# Picobox.net
KiCad netlist of a schematic drawn in EasyEDA
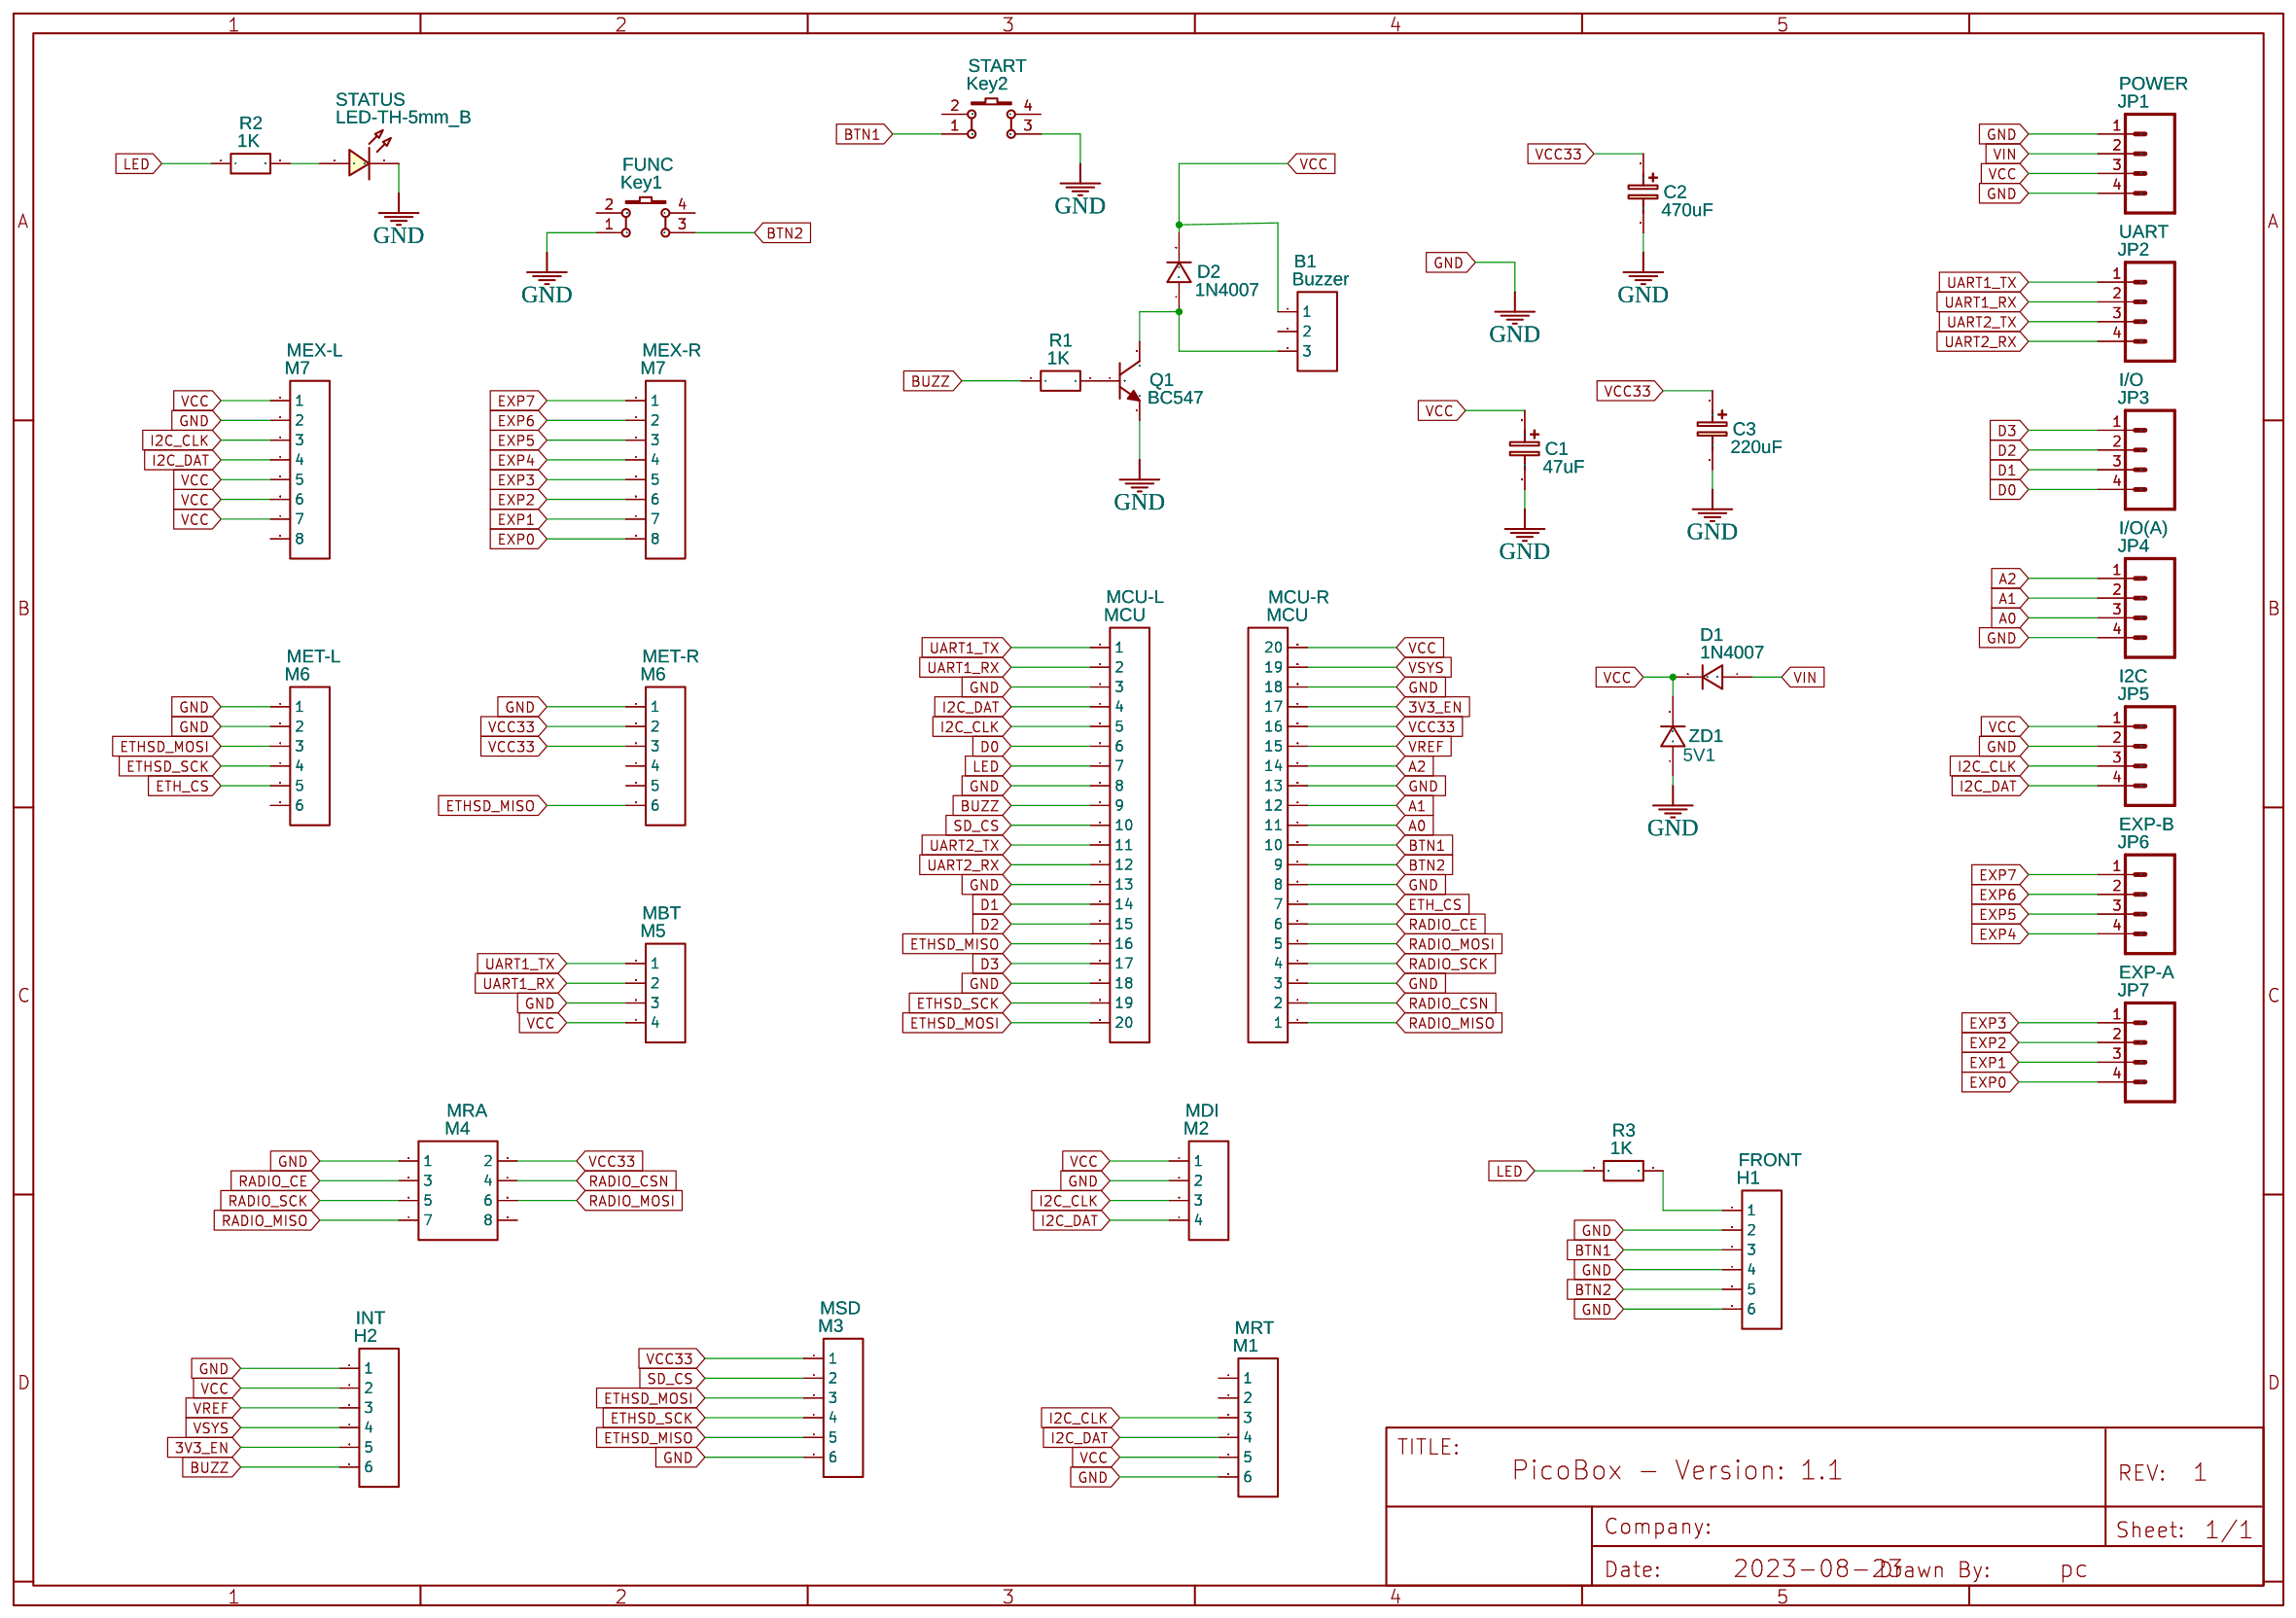
[diagram p0: schematic sheet]

(export (version "E")
  (design (tool "Eeschema 10.0.6"))
  (components
    (comp (ref "B1")
      (value "Buzzer")
      (fields (field (name "BOM_Supplier Part") "C146690"))
      (libsource (lib "") (part "HDR-F-2.54_1x3"))
    )
    (comp (ref "C1") (value "47uF") (libsource (lib "") (part "C_Tan_SMD_A_EU")))
    (comp (ref "C2") (value "470uF") (libsource (lib "") (part "C_Tan_SMD_A_EU")))
    (comp (ref "C3") (value "220uF") (libsource (lib "") (part "C_Tan_SMD_A_EU")))
    (comp (ref "D1")
      (value "1N4007")
      (fields (field (name "BOM_Manufacturer Part") "1N4007W") (field (name "BOM_Supplier Part") "C328592"))
      (libsource (lib "") (part "1N4007W_1"))
    )
    (comp (ref "D2")
      (value "1N4007")
      (fields (field (name "BOM_Manufacturer Part") "1N4007W") (field (name "BOM_Supplier Part") "C328592"))
      (libsource (lib "") (part "1N4007W"))
    )
    (comp (ref "EXP-A") (value "JP7") (libsource (lib "") (part "M04SCREW_4")))
    (comp (ref "EXP-B") (value "JP6") (libsource (lib "") (part "M04SCREW")))
    (comp (ref "FRONT")
      (value "H1")
      (fields (field (name "BOM_Supplier Part") "C40877"))
      (libsource (lib "") (part "HDR-F-2.54_1x6_5"))
    )
    (comp (ref "FUNC")
      (value "Key1")
      (fields
        (field (name "BOM_Manufacturer Part") "K2-1102DP-E4SW-04")
        (field (name "BOM_Supplier Part") "C136684")
      )
      (libsource (lib "") (part "K4-6×6_TH"))
    )
    (comp (ref "I/O") (value "JP3") (libsource (lib "") (part "M04SCREW_3")))
    (comp (ref "I/O(A)") (value "JP4") (libsource (lib "") (part "M04SCREW_1")))
    (comp (ref "I2C") (value "JP5") (libsource (lib "") (part "M04SCREW_5")))
    (comp (ref "INT")
      (value "H2")
      (fields (field (name "BOM_Supplier Part") "C40877"))
      (libsource (lib "") (part "HDR-F-2.54_1x6"))
    )
    (comp (ref "MBT")
      (value "M5")
      (fields (field (name "BOM_Supplier Part") "C225501"))
      (libsource (lib "") (part "HDR-F-2.54_1x4_1"))
    )
    (comp (ref "MCU-L")
      (value "MCU")
      (fields (field (name "BOM_Supplier Part") "C50984"))
      (libsource (lib "") (part "HDR-F-2.54_1x20_1"))
    )
    (comp (ref "MCU-R")
      (value "MCU")
      (fields (field (name "BOM_Supplier Part") "C50984"))
      (libsource (lib "") (part "HDR-F-2.54_1x20"))
    )
    (comp (ref "MDI")
      (value "M2")
      (fields (field (name "BOM_Supplier Part") "C225501"))
      (libsource (lib "") (part "HDR-F-2.54_1x4"))
    )
    (comp (ref "MET-L")
      (value "M6")
      (fields (field (name "BOM_Supplier Part") "C40877"))
      (libsource (lib "") (part "HDR-F-2.54_1x6_3"))
    )
    (comp (ref "MET-R")
      (value "M6")
      (fields (field (name "BOM_Supplier Part") "C40877"))
      (libsource (lib "") (part "HDR-F-2.54_1x6_1"))
    )
    (comp (ref "MEX-L")
      (value "M7")
      (fields (field (name "BOM_Supplier Part") "C225505"))
      (libsource (lib "") (part "HDR-F-2.54_1x8_1"))
    )
    (comp (ref "MEX-R")
      (value "M7")
      (fields (field (name "BOM_Supplier Part") "C225505"))
      (libsource (lib "") (part "HDR-F-2.54_1x8"))
    )
    (comp (ref "MRA")
      (value "M4")
      (fields (field (name "BOM_Supplier Part") "C239344"))
      (libsource (lib "") (part "HDR-F-2.54_2x4"))
    )
    (comp (ref "MRT")
      (value "M1")
      (fields (field (name "BOM_Supplier Part") "C40877"))
      (libsource (lib "") (part "HDR-F-2.54_1x6_2"))
    )
    (comp (ref "MSD")
      (value "M3")
      (fields (field (name "BOM_Supplier Part") "C40877"))
      (libsource (lib "") (part "HDR-F-2.54_1x6_4"))
    )
    (comp (ref "POWER") (value "JP1") (libsource (lib "") (part "M04SCREW_2")))
    (comp (ref "Q1")
      (value "BC547")
      (fields
        (field (name "BOM_Manufacturer Part") "2n3904S-RTK/PS")
        (field (name "BOM_Supplier Part") "C18536")
      )
      (libsource (lib "") (part "2N3904(SOT-23)"))
    )
    (comp (ref "R1") (value "1K") (libsource (lib "") (part "R_0603_EU")))
    (comp (ref "R2") (value "1K") (libsource (lib "") (part "R_0603_EU")))
    (comp (ref "R3") (value "1K") (libsource (lib "") (part "R_0603_EU")))
    (comp (ref "START")
      (value "Key2")
      (fields
        (field (name "BOM_Manufacturer Part") "K2-1102DP-E4SW-04")
        (field (name "BOM_Supplier Part") "C136684")
      )
      (libsource (lib "") (part "K4-6×6_TH_1"))
    )
    (comp (ref "STATUS")
      (value "LED-TH-5mm_B")
      (fields
        (field (name "BOM_Manufacturer Part") "333-2SYGD/S530-E2")
        (field (name "BOM_Supplier Part") "C88163")
      )
      (libsource (lib "") (part "LED-TH-5mm_G"))
    )
    (comp (ref "UART") (value "JP2") (libsource (lib "") (part "M04SCREW_6")))
    (comp (ref "ZD1")
      (value "1N4001")
      (fields (field (name "BOM_Manufacturer Part") "1N4007W") (field (name "BOM_Supplier Part") "C328592"))
      (libsource (lib "") (part "1N4007W_2"))
    )
  )
  (nets
    (net (code "1") (name "3V3_EN") (class "Default")
      (node (ref "INT") (pin "5") (pinfunction "5_5") (pintype "input"))
      (node (ref "MCU-R") (pin "17") (pinfunction "17_17") (pintype "unspecified"))
    )
    (net (code "2") (name "A0") (class "Default")
      (node (ref "I/O(A)") (pin "3") (pinfunction "3_3") (pintype "bidirectional"))
      (node (ref "MCU-R") (pin "11") (pinfunction "11_11") (pintype "unspecified"))
    )
    (net (code "3") (name "A1") (class "Default")
      (node (ref "I/O(A)") (pin "2") (pinfunction "2_2") (pintype "bidirectional"))
      (node (ref "MCU-R") (pin "12") (pinfunction "12_12") (pintype "unspecified"))
    )
    (net (code "4") (name "A2") (class "Default")
      (node (ref "I/O(A)") (pin "1") (pinfunction "1_1") (pintype "bidirectional"))
      (node (ref "MCU-R") (pin "14") (pinfunction "14_14") (pintype "unspecified"))
    )
    (net (code "5") (name "BTN1") (class "Default")
      (node (ref "FRONT") (pin "3") (pinfunction "3_3") (pintype "input"))
      (node (ref "MCU-R") (pin "10") (pinfunction "10_10") (pintype "unspecified"))
      (node (ref "START") (pin "1") (pinfunction "1_1") (pintype "unspecified"))
    )
    (net (code "6") (name "BTN2") (class "Default")
      (node (ref "FRONT") (pin "5") (pinfunction "5_5") (pintype "input"))
      (node (ref "FUNC") (pin "3") (pinfunction "3_3") (pintype "unspecified"))
      (node (ref "MCU-R") (pin "9") (pinfunction "9_9") (pintype "unspecified"))
    )
    (net (code "7") (name "BUZZ") (class "Default")
      (node (ref "INT") (pin "6") (pinfunction "6_6") (pintype "input"))
      (node (ref "MCU-L") (pin "9") (pinfunction "9_9") (pintype "unspecified"))
      (node (ref "R1") (pin "1") (pinfunction "1_1") (pintype "unspecified"))
    )
    (net (code "8") (name "D0") (class "Default")
      (node (ref "I/O") (pin "4") (pinfunction "4_4") (pintype "bidirectional"))
      (node (ref "MCU-L") (pin "6") (pinfunction "6_6") (pintype "unspecified"))
    )
    (net (code "9") (name "D1") (class "Default")
      (node (ref "I/O") (pin "3") (pinfunction "3_3") (pintype "bidirectional"))
      (node (ref "MCU-L") (pin "14") (pinfunction "14_14") (pintype "unspecified"))
    )
    (net (code "10") (name "D2") (class "Default")
      (node (ref "I/O") (pin "2") (pinfunction "2_2") (pintype "bidirectional"))
      (node (ref "MCU-L") (pin "15") (pinfunction "15_15") (pintype "unspecified"))
    )
    (net (code "11") (name "D3") (class "Default")
      (node (ref "I/O") (pin "1") (pinfunction "1_1") (pintype "bidirectional"))
      (node (ref "MCU-L") (pin "17") (pinfunction "17_17") (pintype "unspecified"))
    )
    (net (code "12") (name "ETHSD_MISO") (class "Default")
      (node (ref "MCU-L") (pin "16") (pinfunction "16_16") (pintype "unspecified"))
      (node (ref "MET-R") (pin "6") (pinfunction "6_6") (pintype "input"))
      (node (ref "MSD") (pin "5") (pinfunction "5_5") (pintype "input"))
    )
    (net (code "13") (name "ETHSD_MOSI") (class "Default")
      (node (ref "MCU-L") (pin "20") (pinfunction "20_20") (pintype "unspecified"))
      (node (ref "MET-L") (pin "3") (pinfunction "3_3") (pintype "input"))
      (node (ref "MSD") (pin "3") (pinfunction "3_3") (pintype "input"))
    )
    (net (code "14") (name "ETHSD_SCK") (class "Default")
      (node (ref "MCU-L") (pin "19") (pinfunction "19_19") (pintype "unspecified"))
      (node (ref "MET-L") (pin "4") (pinfunction "4_4") (pintype "input"))
      (node (ref "MSD") (pin "4") (pinfunction "4_4") (pintype "input"))
    )
    (net (code "15") (name "ETH_CS") (class "Default")
      (node (ref "MCU-R") (pin "7") (pinfunction "7_7") (pintype "unspecified"))
      (node (ref "MET-L") (pin "5") (pinfunction "5_5") (pintype "input"))
    )
    (net (code "16") (name "EXP0") (class "Default")
      (node (ref "EXP-A") (pin "4") (pinfunction "4_4") (pintype "bidirectional"))
      (node (ref "MEX-R") (pin "8") (pinfunction "8_8") (pintype "unspecified"))
    )
    (net (code "17") (name "EXP1") (class "Default")
      (node (ref "EXP-A") (pin "3") (pinfunction "3_3") (pintype "bidirectional"))
      (node (ref "MEX-R") (pin "7") (pinfunction "7_7") (pintype "unspecified"))
    )
    (net (code "18") (name "EXP2") (class "Default")
      (node (ref "EXP-A") (pin "2") (pinfunction "2_2") (pintype "bidirectional"))
      (node (ref "MEX-R") (pin "6") (pinfunction "6_6") (pintype "unspecified"))
    )
    (net (code "19") (name "EXP3") (class "Default")
      (node (ref "EXP-A") (pin "1") (pinfunction "1_1") (pintype "bidirectional"))
      (node (ref "MEX-R") (pin "5") (pinfunction "5_5") (pintype "unspecified"))
    )
    (net (code "20") (name "EXP4") (class "Default")
      (node (ref "EXP-B") (pin "4") (pinfunction "4_4") (pintype "bidirectional"))
      (node (ref "MEX-R") (pin "4") (pinfunction "4_4") (pintype "unspecified"))
    )
    (net (code "21") (name "EXP5") (class "Default")
      (node (ref "EXP-B") (pin "3") (pinfunction "3_3") (pintype "bidirectional"))
      (node (ref "MEX-R") (pin "3") (pinfunction "3_3") (pintype "unspecified"))
    )
    (net (code "22") (name "EXP6") (class "Default")
      (node (ref "EXP-B") (pin "2") (pinfunction "2_2") (pintype "bidirectional"))
      (node (ref "MEX-R") (pin "2") (pinfunction "2_2") (pintype "unspecified"))
    )
    (net (code "23") (name "EXP7") (class "Default")
      (node (ref "EXP-B") (pin "1") (pinfunction "1_1") (pintype "bidirectional"))
      (node (ref "MEX-R") (pin "1") (pinfunction "1_1") (pintype "unspecified"))
    )
    (net (code "24") (name "GND") (class "Default")
      (node (ref "C1") (pin "VSS") (pinfunction "2_VSS") (pintype "unspecified"))
      (node (ref "C2") (pin "VSS") (pinfunction "2_VSS") (pintype "unspecified"))
      (node (ref "C3") (pin "VSS") (pinfunction "2_VSS") (pintype "unspecified"))
      (node (ref "FRONT") (pin "2") (pinfunction "2_2") (pintype "input"))
      (node (ref "FRONT") (pin "4") (pinfunction "4_4") (pintype "input"))
      (node (ref "FRONT") (pin "6") (pinfunction "6_6") (pintype "input"))
      (node (ref "FUNC") (pin "1") (pinfunction "1_1") (pintype "unspecified"))
      (node (ref "I/O(A)") (pin "4") (pinfunction "4_4") (pintype "bidirectional"))
      (node (ref "I2C") (pin "2") (pinfunction "2_2") (pintype "bidirectional"))
      (node (ref "INT") (pin "1") (pinfunction "1_1") (pintype "input"))
      (node (ref "MBT") (pin "3") (pinfunction "3_3") (pintype "unspecified"))
      (node (ref "MCU-L") (pin "13") (pinfunction "13_13") (pintype "unspecified"))
      (node (ref "MCU-L") (pin "18") (pinfunction "18_18") (pintype "unspecified"))
      (node (ref "MCU-L") (pin "3") (pinfunction "3_3") (pintype "unspecified"))
      (node (ref "MCU-L") (pin "8") (pinfunction "8_8") (pintype "unspecified"))
      (node (ref "MCU-R") (pin "13") (pinfunction "13_13") (pintype "unspecified"))
      (node (ref "MCU-R") (pin "18") (pinfunction "18_18") (pintype "unspecified"))
      (node (ref "MCU-R") (pin "3") (pinfunction "3_3") (pintype "unspecified"))
      (node (ref "MCU-R") (pin "8") (pinfunction "8_8") (pintype "unspecified"))
      (node (ref "MDI") (pin "2") (pinfunction "2_2") (pintype "unspecified"))
      (node (ref "MET-L") (pin "1") (pinfunction "1_1") (pintype "input"))
      (node (ref "MET-L") (pin "2") (pinfunction "2_2") (pintype "input"))
      (node (ref "MET-R") (pin "1") (pinfunction "1_1") (pintype "input"))
      (node (ref "MEX-L") (pin "2") (pinfunction "2_2") (pintype "unspecified"))
      (node (ref "MRA") (pin "1") (pinfunction "1_1") (pintype "unspecified"))
      (node (ref "MRT") (pin "6") (pinfunction "6_6") (pintype "input"))
      (node (ref "MSD") (pin "6") (pinfunction "6_6") (pintype "input"))
      (node (ref "POWER") (pin "1") (pinfunction "1_1") (pintype "bidirectional"))
      (node (ref "POWER") (pin "4") (pinfunction "4_4") (pintype "bidirectional"))
      (node (ref "Q1") (pin "1") (pinfunction "E_1") (pintype "input"))
      (node (ref "START") (pin "3") (pinfunction "3_3") (pintype "unspecified"))
      (node (ref "STATUS") (pin "2") (pinfunction "2_2") (pintype "unspecified"))
      (node (ref "ZD1") (pin "A") (pinfunction "2_A") (pintype "unspecified"))
    )
    (net (code "25") (name "I2C_CLK") (class "Default")
      (node (ref "I2C") (pin "3") (pinfunction "3_3") (pintype "bidirectional"))
      (node (ref "MCU-L") (pin "5") (pinfunction "5_5") (pintype "unspecified"))
      (node (ref "MDI") (pin "3") (pinfunction "3_3") (pintype "unspecified"))
      (node (ref "MEX-L") (pin "3") (pinfunction "3_3") (pintype "unspecified"))
      (node (ref "MRT") (pin "3") (pinfunction "3_3") (pintype "input"))
    )
    (net (code "26") (name "I2C_DAT") (class "Default")
      (node (ref "I2C") (pin "4") (pinfunction "4_4") (pintype "bidirectional"))
      (node (ref "MCU-L") (pin "4") (pinfunction "4_4") (pintype "unspecified"))
      (node (ref "MDI") (pin "4") (pinfunction "4_4") (pintype "unspecified"))
      (node (ref "MEX-L") (pin "4") (pinfunction "4_4") (pintype "unspecified"))
      (node (ref "MRT") (pin "4") (pinfunction "4_4") (pintype "input"))
    )
    (net (code "27") (name "LED") (class "Default")
      (node (ref "MCU-L") (pin "7") (pinfunction "7_7") (pintype "unspecified"))
      (node (ref "R2") (pin "1") (pinfunction "1_1") (pintype "unspecified"))
      (node (ref "R3") (pin "1") (pinfunction "1_1") (pintype "unspecified"))
    )
    (net (code "28") (name "Net-(B1-3)") (class "Default")
      (node (ref "B1") (pin "2") (pinfunction "3_2") (pintype "input"))
      (node (ref "D2") (pin "A") (pinfunction "2_A") (pintype "unspecified"))
      (node (ref "Q1") (pin "3") (pinfunction "C_3") (pintype "input"))
    )
    (net (code "29") (name "Net-(FRONT-Pad1)") (class "Default")
      (node (ref "FRONT") (pin "1") (pinfunction "1_1") (pintype "input"))
      (node (ref "R3") (pin "2") (pinfunction "2_2") (pintype "unspecified"))
    )
    (net (code "30") (name "Net-(Q1-B)") (class "Default")
      (node (ref "Q1") (pin "2") (pinfunction "B_2") (pintype "input"))
      (node (ref "R1") (pin "2") (pinfunction "2_2") (pintype "unspecified"))
    )
    (net (code "31") (name "Net-(R2-Pad2)") (class "Default")
      (node (ref "R2") (pin "2") (pinfunction "2_2") (pintype "unspecified"))
      (node (ref "STATUS") (pin "1") (pinfunction "1_1") (pintype "unspecified"))
    )
    (net (code "32") (name "RADIO_CE") (class "Default")
      (node (ref "MCU-R") (pin "6") (pinfunction "6_6") (pintype "unspecified"))
      (node (ref "MRA") (pin "3") (pinfunction "3_3") (pintype "unspecified"))
    )
    (net (code "33") (name "RADIO_CSN") (class "Default")
      (node (ref "MCU-R") (pin "2") (pinfunction "2_2") (pintype "unspecified"))
      (node (ref "MRA") (pin "4") (pinfunction "4_4") (pintype "unspecified"))
    )
    (net (code "34") (name "RADIO_MISO") (class "Default")
      (node (ref "MCU-R") (pin "1") (pinfunction "1_1") (pintype "unspecified"))
      (node (ref "MRA") (pin "7") (pinfunction "7_7") (pintype "unspecified"))
    )
    (net (code "35") (name "RADIO_MOSI") (class "Default")
      (node (ref "MCU-R") (pin "5") (pinfunction "5_5") (pintype "unspecified"))
      (node (ref "MRA") (pin "6") (pinfunction "6_6") (pintype "unspecified"))
    )
    (net (code "36") (name "RADIO_SCK") (class "Default")
      (node (ref "MCU-R") (pin "4") (pinfunction "4_4") (pintype "unspecified"))
      (node (ref "MRA") (pin "5") (pinfunction "5_5") (pintype "unspecified"))
    )
    (net (code "37") (name "SD_CS") (class "Default")
      (node (ref "MCU-L") (pin "10") (pinfunction "10_10") (pintype "unspecified"))
      (node (ref "MSD") (pin "2") (pinfunction "2_2") (pintype "input"))
    )
    (net (code "38") (name "UART1_RX") (class "Default")
      (node (ref "MBT") (pin "2") (pinfunction "2_2") (pintype "unspecified"))
      (node (ref "MCU-L") (pin "2") (pinfunction "2_2") (pintype "unspecified"))
      (node (ref "UART") (pin "2") (pinfunction "2_2") (pintype "bidirectional"))
    )
    (net (code "39") (name "UART1_TX") (class "Default")
      (node (ref "MBT") (pin "1") (pinfunction "1_1") (pintype "unspecified"))
      (node (ref "MCU-L") (pin "1") (pinfunction "1_1") (pintype "unspecified"))
      (node (ref "UART") (pin "1") (pinfunction "1_1") (pintype "bidirectional"))
    )
    (net (code "40") (name "UART2_RX") (class "Default")
      (node (ref "MCU-L") (pin "12") (pinfunction "12_12") (pintype "unspecified"))
      (node (ref "UART") (pin "4") (pinfunction "4_4") (pintype "bidirectional"))
    )
    (net (code "41") (name "UART2_TX") (class "Default")
      (node (ref "MCU-L") (pin "11") (pinfunction "11_11") (pintype "unspecified"))
      (node (ref "UART") (pin "3") (pinfunction "3_3") (pintype "bidirectional"))
    )
    (net (code "42") (name "VCC") (class "Default")
      (node (ref "B1") (pin "1") (pinfunction "1_1") (pintype "input"))
      (node (ref "C1") (pin "VDD") (pinfunction "1_VDD") (pintype "unspecified"))
      (node (ref "D1") (pin "C") (pinfunction "1_C") (pintype "unspecified"))
      (node (ref "D2") (pin "C") (pinfunction "1_C") (pintype "unspecified"))
      (node (ref "I2C") (pin "1") (pinfunction "1_1") (pintype "bidirectional"))
      (node (ref "INT") (pin "2") (pinfunction "2_2") (pintype "input"))
      (node (ref "MBT") (pin "4") (pinfunction "4_4") (pintype "unspecified"))
      (node (ref "MCU-R") (pin "20") (pinfunction "20_20") (pintype "unspecified"))
      (node (ref "MDI") (pin "1") (pinfunction "1_1") (pintype "unspecified"))
      (node (ref "MEX-L") (pin "1") (pinfunction "1_1") (pintype "unspecified"))
      (node (ref "MEX-L") (pin "5") (pinfunction "5_5") (pintype "unspecified"))
      (node (ref "MEX-L") (pin "6") (pinfunction "6_6") (pintype "unspecified"))
      (node (ref "MEX-L") (pin "7") (pinfunction "7_7") (pintype "unspecified"))
      (node (ref "MRT") (pin "5") (pinfunction "5_5") (pintype "input"))
      (node (ref "POWER") (pin "3") (pinfunction "3_3") (pintype "bidirectional"))
      (node (ref "ZD1") (pin "C") (pinfunction "1_C") (pintype "unspecified"))
    )
    (net (code "43") (name "VCC33") (class "Default")
      (node (ref "C2") (pin "VDD") (pinfunction "1_VDD") (pintype "unspecified"))
      (node (ref "C3") (pin "VDD") (pinfunction "1_VDD") (pintype "unspecified"))
      (node (ref "MCU-R") (pin "16") (pinfunction "16_16") (pintype "unspecified"))
      (node (ref "MET-R") (pin "2") (pinfunction "2_2") (pintype "input"))
      (node (ref "MET-R") (pin "3") (pinfunction "3_3") (pintype "input"))
      (node (ref "MRA") (pin "2") (pinfunction "2_2") (pintype "unspecified"))
      (node (ref "MSD") (pin "1") (pinfunction "1_1") (pintype "input"))
    )
    (net (code "44") (name "VIN") (class "Default")
      (node (ref "D1") (pin "A") (pinfunction "2_A") (pintype "unspecified"))
      (node (ref "POWER") (pin "2") (pinfunction "2_2") (pintype "bidirectional"))
    )
    (net (code "45") (name "VREF") (class "Default")
      (node (ref "INT") (pin "3") (pinfunction "3_3") (pintype "input"))
      (node (ref "MCU-R") (pin "15") (pinfunction "15_15") (pintype "unspecified"))
    )
    (net (code "46") (name "VSYS") (class "Default")
      (node (ref "INT") (pin "4") (pinfunction "4_4") (pintype "input"))
      (node (ref "MCU-R") (pin "19") (pinfunction "19_19") (pintype "unspecified"))
    )
    (net (code "47") (name "unconnected-(B1-Pad2)") (class "Default")
      (node (ref "B1") (pin "2") (pinfunction "2_2") (pintype "input"))
    )
    (net (code "48") (name "unconnected-(FUNC-Pad2)") (class "Default")
      (node (ref "FUNC") (pin "2") (pinfunction "2_2") (pintype "unspecified"))
    )
    (net (code "49") (name "unconnected-(FUNC-Pad4)") (class "Default")
      (node (ref "FUNC") (pin "4") (pinfunction "4_4") (pintype "unspecified"))
    )
    (net (code "50") (name "unconnected-(MET-L-Pad6)") (class "Default")
      (node (ref "MET-L") (pin "6") (pinfunction "6_6") (pintype "input"))
    )
    (net (code "51") (name "unconnected-(MET-R-Pad4)") (class "Default")
      (node (ref "MET-R") (pin "4") (pinfunction "4_4") (pintype "input"))
    )
    (net (code "52") (name "unconnected-(MET-R-Pad5)") (class "Default")
      (node (ref "MET-R") (pin "5") (pinfunction "5_5") (pintype "input"))
    )
    (net (code "53") (name "unconnected-(MEX-L-Pad8)") (class "Default")
      (node (ref "MEX-L") (pin "8") (pinfunction "8_8") (pintype "unspecified"))
    )
    (net (code "54") (name "unconnected-(MRA-Pad8)") (class "Default")
      (node (ref "MRA") (pin "8") (pinfunction "8_8") (pintype "unspecified"))
    )
    (net (code "55") (name "unconnected-(MRT-Pad1)") (class "Default")
      (node (ref "MRT") (pin "1") (pinfunction "1_1") (pintype "input"))
    )
    (net (code "56") (name "unconnected-(MRT-Pad2)") (class "Default")
      (node (ref "MRT") (pin "2") (pinfunction "2_2") (pintype "input"))
    )
    (net (code "57") (name "unconnected-(START-Pad2)") (class "Default")
      (node (ref "START") (pin "2") (pinfunction "2_2") (pintype "unspecified"))
    )
    (net (code "58") (name "unconnected-(START-Pad4)") (class "Default")
      (node (ref "START") (pin "4") (pinfunction "4_4") (pintype "unspecified"))
    )
  )
)
